# MyBoard_v1.net
KiCad netlist of a schematic drawn in Altium Designer
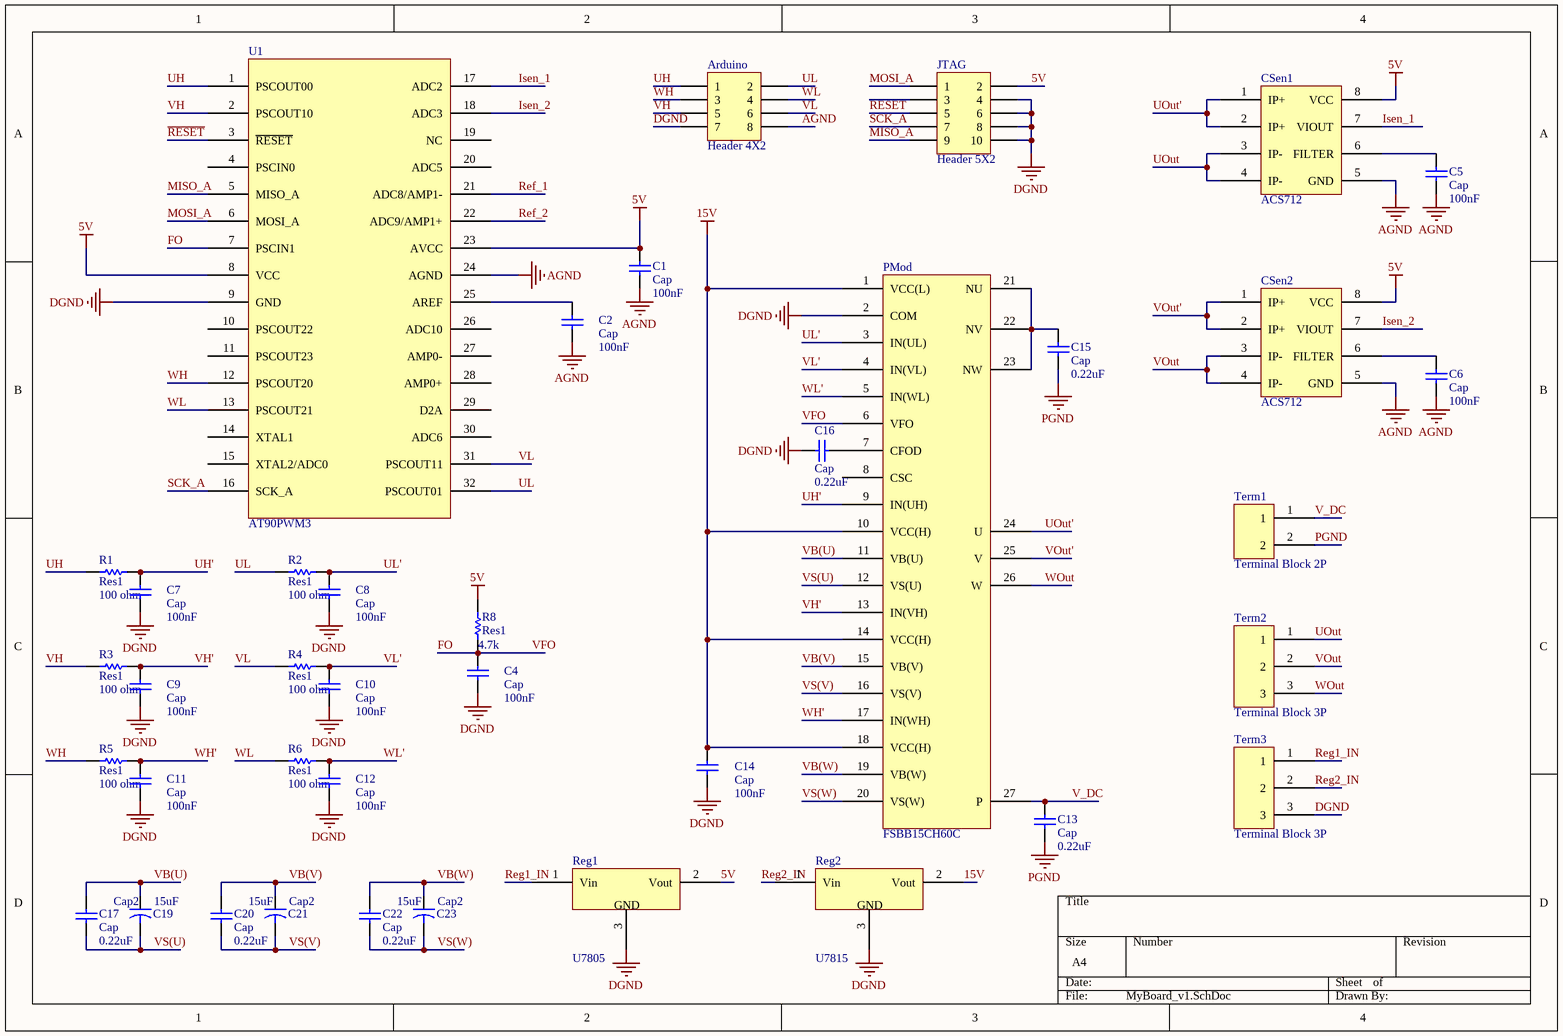
[diagram p0: MyBoard_v1.SchDoc]

(export (version "E")
  (design (tool "Eeschema 10.0.6"))
  (components
    (comp (ref "Arduino")
      (value "Header 4X2")
      (footprint "HDR2X4")
      (description "Header, 4-Pin, Dual row")
      (fields (field (name "PUBLISHER") "Altium Limited"))
      (libsource (lib "Miscellaneous Connectors") (part "Header 4X2"))
    )
    (comp (ref "C1")
      (value "Cap")
      (footprint "NPolar_Cap")
      (description "Capacitor")
      (fields (field (name "ALTIUM_VALUE") "100nF") (field (name "PUBLISHER") "Altium Limited"))
      (libsource (lib "Miscellaneous Devices") (part "Cap"))
    )
    (comp (ref "C2")
      (value "Cap")
      (footprint "NPolar_Cap")
      (description "Capacitor")
      (fields (field (name "ALTIUM_VALUE") "100nF") (field (name "PUBLISHER") "Altium Limited"))
      (libsource (lib "Miscellaneous Devices") (part "Cap"))
    )
    (comp (ref "C4")
      (value "Cap")
      (footprint "NPolar_Cap")
      (description "Capacitor")
      (fields (field (name "ALTIUM_VALUE") "100nF") (field (name "PUBLISHER") "Altium Limited"))
      (libsource (lib "Miscellaneous Devices") (part "Cap"))
    )
    (comp (ref "C5")
      (value "Cap")
      (footprint "NPolar_Cap")
      (description "Capacitor")
      (fields (field (name "ALTIUM_VALUE") "100nF") (field (name "PUBLISHER") "Altium Limited"))
      (libsource (lib "Miscellaneous Devices") (part "Cap"))
    )
    (comp (ref "C6")
      (value "Cap")
      (footprint "NPolar_Cap")
      (description "Capacitor")
      (fields (field (name "ALTIUM_VALUE") "100nF") (field (name "PUBLISHER") "Altium Limited"))
      (libsource (lib "Miscellaneous Devices") (part "Cap"))
    )
    (comp (ref "C7")
      (value "Cap")
      (footprint "NPolar_Cap")
      (description "Capacitor")
      (fields (field (name "ALTIUM_VALUE") "100nF") (field (name "PUBLISHER") "Altium Limited"))
      (libsource (lib "Miscellaneous Devices") (part "Cap"))
    )
    (comp (ref "C8")
      (value "Cap")
      (footprint "NPolar_Cap")
      (description "Capacitor")
      (fields (field (name "ALTIUM_VALUE") "100nF") (field (name "PUBLISHER") "Altium Limited"))
      (libsource (lib "Miscellaneous Devices") (part "Cap"))
    )
    (comp (ref "C9")
      (value "Cap")
      (footprint "NPolar_Cap")
      (description "Capacitor")
      (fields (field (name "ALTIUM_VALUE") "100nF") (field (name "PUBLISHER") "Altium Limited"))
      (libsource (lib "Miscellaneous Devices") (part "Cap"))
    )
    (comp (ref "C10")
      (value "Cap")
      (footprint "NPolar_Cap")
      (description "Capacitor")
      (fields (field (name "ALTIUM_VALUE") "100nF") (field (name "PUBLISHER") "Altium Limited"))
      (libsource (lib "Miscellaneous Devices") (part "Cap"))
    )
    (comp (ref "C11")
      (value "Cap")
      (footprint "NPolar_Cap")
      (description "Capacitor")
      (fields (field (name "ALTIUM_VALUE") "100nF") (field (name "PUBLISHER") "Altium Limited"))
      (libsource (lib "Miscellaneous Devices") (part "Cap"))
    )
    (comp (ref "C12")
      (value "Cap")
      (footprint "NPolar_Cap")
      (description "Capacitor")
      (fields (field (name "ALTIUM_VALUE") "100nF") (field (name "PUBLISHER") "Altium Limited"))
      (libsource (lib "Miscellaneous Devices") (part "Cap"))
    )
    (comp (ref "C13")
      (value "Cap")
      (footprint "NPolar_Cap")
      (description "Capacitor")
      (fields (field (name "ALTIUM_VALUE") "0.22uF") (field (name "PUBLISHER") "Altium Limited"))
      (libsource (lib "Miscellaneous Devices") (part "Cap"))
    )
    (comp (ref "C14")
      (value "Cap")
      (footprint "NPolar_Cap")
      (description "Capacitor")
      (fields (field (name "ALTIUM_VALUE") "100nF") (field (name "PUBLISHER") "Altium Limited"))
      (libsource (lib "Miscellaneous Devices") (part "Cap"))
    )
    (comp (ref "C15")
      (value "Cap")
      (footprint "NPolar_Cap")
      (description "Capacitor")
      (fields (field (name "ALTIUM_VALUE") "0.22uF") (field (name "PUBLISHER") "Altium Limited"))
      (libsource (lib "Miscellaneous Devices") (part "Cap"))
    )
    (comp (ref "C16")
      (value "Cap")
      (footprint "NPolar_Cap")
      (description "Capacitor")
      (fields (field (name "ALTIUM_VALUE") "0.22uF") (field (name "PUBLISHER") "Altium Limited"))
      (libsource (lib "Miscellaneous Devices") (part "Cap"))
    )
    (comp (ref "C17")
      (value "Cap")
      (footprint "NPolar_Cap")
      (description "Capacitor")
      (fields (field (name "ALTIUM_VALUE") "0.22uF") (field (name "PUBLISHER") "Altium Limited"))
      (libsource (lib "Miscellaneous Devices") (part "Cap"))
    )
    (comp (ref "C19")
      (value "Cap2")
      (footprint "Polar_Cap")
      (description "Capacitor")
      (fields (field (name "ALTIUM_VALUE") "15uF") (field (name "PUBLISHER") "Altium Limited"))
      (libsource (lib "Miscellaneous Devices") (part "Cap2"))
    )
    (comp (ref "C20")
      (value "Cap")
      (footprint "NPolar_Cap")
      (description "Capacitor")
      (fields (field (name "ALTIUM_VALUE") "0.22uF") (field (name "PUBLISHER") "Altium Limited"))
      (libsource (lib "Miscellaneous Devices") (part "Cap"))
    )
    (comp (ref "C21")
      (value "Cap2")
      (footprint "Polar_Cap")
      (description "Capacitor")
      (fields (field (name "ALTIUM_VALUE") "15uF") (field (name "PUBLISHER") "Altium Limited"))
      (libsource (lib "Miscellaneous Devices") (part "Cap2"))
    )
    (comp (ref "C22")
      (value "Cap")
      (footprint "NPolar_Cap")
      (description "Capacitor")
      (fields (field (name "ALTIUM_VALUE") "0.22uF") (field (name "PUBLISHER") "Altium Limited"))
      (libsource (lib "Miscellaneous Devices") (part "Cap"))
    )
    (comp (ref "C23")
      (value "Cap2")
      (footprint "Polar_Cap")
      (description "Capacitor")
      (fields (field (name "ALTIUM_VALUE") "15uF") (field (name "PUBLISHER") "Altium Limited"))
      (libsource (lib "Miscellaneous Devices") (part "Cap2"))
    )
    (comp (ref "CSen1")
      (value "ACS712")
      (footprint "FYP:ACS712")
      (libsource (lib "MyBoard_v1") (part "ACS711"))
    )
    (comp (ref "CSen2")
      (value "ACS712")
      (footprint "FYP:ACS712")
      (libsource (lib "MyBoard_v1") (part "ACS711"))
    )
    (comp (ref "JTAG")
      (value "Header 5X2")
      (footprint "HDR2X5")
      (description "Header, 5-Pin, Dual row")
      (fields (field (name "PUBLISHER") "Altium Limited"))
      (libsource (lib "Miscellaneous Connectors") (part "Header 5X2"))
    )
    (comp (ref "PMod")
      (value "FSBB15CH60C")
      (footprint "FYP:FSBB20CH60F")
      (libsource (lib "MyBoard_v1") (part "FSBB15CH60C"))
    )
    (comp (ref "R1")
      (value "Res1")
      (footprint "AXIAL-0.3")
      (description "Resistor")
      (fields (field (name "ALTIUM_VALUE") "100 ohm") (field (name "PUBLISHER") "Altium Limited"))
      (libsource (lib "Miscellaneous Devices") (part "Res1"))
    )
    (comp (ref "R2")
      (value "Res1")
      (footprint "AXIAL-0.3")
      (description "Resistor")
      (fields (field (name "ALTIUM_VALUE") "100 ohm") (field (name "PUBLISHER") "Altium Limited"))
      (libsource (lib "Miscellaneous Devices") (part "Res1"))
    )
    (comp (ref "R3")
      (value "Res1")
      (footprint "AXIAL-0.3")
      (description "Resistor")
      (fields (field (name "ALTIUM_VALUE") "100 ohm") (field (name "PUBLISHER") "Altium Limited"))
      (libsource (lib "Miscellaneous Devices") (part "Res1"))
    )
    (comp (ref "R4")
      (value "Res1")
      (footprint "AXIAL-0.3")
      (description "Resistor")
      (fields (field (name "ALTIUM_VALUE") "100 ohm") (field (name "PUBLISHER") "Altium Limited"))
      (libsource (lib "Miscellaneous Devices") (part "Res1"))
    )
    (comp (ref "R5")
      (value "Res1")
      (footprint "AXIAL-0.3")
      (description "Resistor")
      (fields (field (name "ALTIUM_VALUE") "100 ohm") (field (name "PUBLISHER") "Altium Limited"))
      (libsource (lib "Miscellaneous Devices") (part "Res1"))
    )
    (comp (ref "R6")
      (value "Res1")
      (footprint "AXIAL-0.3")
      (description "Resistor")
      (fields (field (name "ALTIUM_VALUE") "100 ohm") (field (name "PUBLISHER") "Altium Limited"))
      (libsource (lib "Miscellaneous Devices") (part "Res1"))
    )
    (comp (ref "R8")
      (value "Res1")
      (footprint "AXIAL-0.3")
      (description "Resistor")
      (fields (field (name "ALTIUM_VALUE") "4.7k") (field (name "PUBLISHER") "Altium Limited"))
      (libsource (lib "Miscellaneous Devices") (part "Res1"))
    )
    (comp (ref "Reg1") (value "U7805") (footprint "FYP:U7800") (libsource (lib "MyBoard_v1") (part "U7800")))
    (comp (ref "Reg2") (value "U7815") (footprint "FYP:U7800") (libsource (lib "MyBoard_v1") (part "U7800")))
    (comp (ref "Term1")
      (value "Terminal Block 2P")
      (footprint "Terminal Block 2 Pin")
      (libsource (lib "MyBoard_v1") (part "Terminal Block 2P"))
    )
    (comp (ref "Term2")
      (value "Terminal Block 3P")
      (footprint "Terminal Block 3 Pin")
      (libsource (lib "MyBoard_v1") (part "Terminal Block 3P"))
    )
    (comp (ref "Term3")
      (value "Terminal Block 3P")
      (footprint "Terminal Block 3 Pin")
      (libsource (lib "MyBoard_v1") (part "Terminal Block 3P"))
    )
    (comp (ref "U1")
      (value "AT90PWM3")
      (footprint "FYP:AT90PWM3B")
      (libsource (lib "MyBoard_v1") (part "AT90PWM3"))
    )
  )
  (nets
    (net (code "1") (name "/FO") (class "Default")
      (node (ref "C4") (pin "2") (pinfunction "2_2") (pintype "passive"))
      (node (ref "PMod") (pin "6") (pinfunction "VFO_6") (pintype "passive"))
      (node (ref "R8") (pin "1") (pinfunction "1_1") (pintype "passive"))
      (node (ref "U1") (pin "7") (pinfunction "PSCIN1_7") (pintype "passive"))
    )
    (net (code "2") (name "/Isen_1") (class "Default")
      (node (ref "CSen1") (pin "7") (pinfunction "VIOUT_7") (pintype "passive"))
      (node (ref "U1") (pin "17") (pinfunction "ADC2_17") (pintype "passive"))
    )
    (net (code "3") (name "/Isen_2") (class "Default")
      (node (ref "CSen2") (pin "7") (pinfunction "VIOUT_7") (pintype "passive"))
      (node (ref "U1") (pin "18") (pinfunction "ADC3_18") (pintype "passive"))
    )
    (net (code "4") (name "/MISO_A") (class "Default")
      (node (ref "JTAG") (pin "9") (pinfunction "9_9") (pintype "passive"))
      (node (ref "U1") (pin "5") (pinfunction "MISO_A_5") (pintype "passive"))
    )
    (net (code "5") (name "/MOSI_A") (class "Default")
      (node (ref "JTAG") (pin "1") (pinfunction "1_1") (pintype "passive"))
      (node (ref "U1") (pin "6") (pinfunction "MOSI_A_6") (pintype "passive"))
    )
    (net (code "6") (name "/Ref_1") (class "Default")
      (node (ref "U1") (pin "21") (pinfunction "ADC8/AMP1-_21") (pintype "passive"))
    )
    (net (code "7") (name "/Ref_2") (class "Default")
      (node (ref "U1") (pin "22") (pinfunction "ADC9/AMP1+_22") (pintype "passive"))
    )
    (net (code "8") (name "/Reg1_IN") (class "Default")
      (node (ref "Reg1") (pin "1") (pinfunction "Vin_1") (pintype "passive"))
      (node (ref "Term3") (pin "1") (pinfunction "1_1") (pintype "passive"))
    )
    (net (code "9") (name "/Reg2_IN") (class "Default")
      (node (ref "Reg2") (pin "1") (pinfunction "Vin_1") (pintype "passive"))
      (node (ref "Term3") (pin "2") (pinfunction "2_2") (pintype "passive"))
    )
    (net (code "10") (name "/SCK_A") (class "Default")
      (node (ref "JTAG") (pin "7") (pinfunction "7_7") (pintype "passive"))
      (node (ref "U1") (pin "16") (pinfunction "SCK_A_16") (pintype "passive"))
    )
    (net (code "11") (name "/UH") (class "Default")
      (node (ref "Arduino") (pin "1") (pinfunction "1_1") (pintype "passive"))
      (node (ref "R1") (pin "1") (pinfunction "1_1") (pintype "passive"))
      (node (ref "U1") (pin "1") (pinfunction "PSCOUT00_1") (pintype "passive"))
    )
    (net (code "12") (name "/UH'") (class "Default")
      (node (ref "C7") (pin "2") (pinfunction "2_2") (pintype "passive"))
      (node (ref "PMod") (pin "9") (pinfunction "IN(UH)_9") (pintype "passive"))
      (node (ref "R1") (pin "2") (pinfunction "2_2") (pintype "passive"))
    )
    (net (code "13") (name "/UL") (class "Default")
      (node (ref "Arduino") (pin "2") (pinfunction "2_2") (pintype "passive"))
      (node (ref "R2") (pin "1") (pinfunction "1_1") (pintype "passive"))
      (node (ref "U1") (pin "32") (pinfunction "PSCOUT01_32") (pintype "passive"))
    )
    (net (code "14") (name "/UL'") (class "Default")
      (node (ref "C8") (pin "2") (pinfunction "2_2") (pintype "passive"))
      (node (ref "PMod") (pin "3") (pinfunction "IN(UL)_3") (pintype "passive"))
      (node (ref "R2") (pin "2") (pinfunction "2_2") (pintype "passive"))
    )
    (net (code "15") (name "/UOut") (class "Default")
      (node (ref "CSen1") (pin "3") (pinfunction "IP-_3") (pintype "passive"))
      (node (ref "CSen1") (pin "4") (pinfunction "IP-_4") (pintype "passive"))
      (node (ref "Term2") (pin "1") (pinfunction "1_1") (pintype "passive"))
    )
    (net (code "16") (name "/UOut'") (class "Default")
      (node (ref "CSen1") (pin "1") (pinfunction "IP+_1") (pintype "passive"))
      (node (ref "CSen1") (pin "2") (pinfunction "IP+_2") (pintype "passive"))
      (node (ref "PMod") (pin "24") (pinfunction "U_24") (pintype "passive"))
    )
    (net (code "17") (name "/VB(U)") (class "Default")
      (node (ref "C17") (pin "2") (pinfunction "2_2") (pintype "passive"))
      (node (ref "C19") (pin "1") (pinfunction "1_1") (pintype "passive"))
      (node (ref "PMod") (pin "11") (pinfunction "VB(U)_11") (pintype "passive"))
    )
    (net (code "18") (name "/VB(V)") (class "Default")
      (node (ref "C20") (pin "2") (pinfunction "2_2") (pintype "passive"))
      (node (ref "C21") (pin "1") (pinfunction "1_1") (pintype "passive"))
      (node (ref "PMod") (pin "15") (pinfunction "VB(V)_15") (pintype "passive"))
    )
    (net (code "19") (name "/VB(W)") (class "Default")
      (node (ref "C22") (pin "2") (pinfunction "2_2") (pintype "passive"))
      (node (ref "C23") (pin "1") (pinfunction "1_1") (pintype "passive"))
      (node (ref "PMod") (pin "19") (pinfunction "VB(W)_19") (pintype "passive"))
    )
    (net (code "20") (name "/VH") (class "Default")
      (node (ref "Arduino") (pin "5") (pinfunction "5_5") (pintype "passive"))
      (node (ref "R3") (pin "1") (pinfunction "1_1") (pintype "passive"))
      (node (ref "U1") (pin "2") (pinfunction "PSCOUT10_2") (pintype "passive"))
    )
    (net (code "21") (name "/VH'") (class "Default")
      (node (ref "C9") (pin "2") (pinfunction "2_2") (pintype "passive"))
      (node (ref "PMod") (pin "13") (pinfunction "IN(VH)_13") (pintype "passive"))
      (node (ref "R3") (pin "2") (pinfunction "2_2") (pintype "passive"))
    )
    (net (code "22") (name "/VL") (class "Default")
      (node (ref "Arduino") (pin "6") (pinfunction "6_6") (pintype "passive"))
      (node (ref "R4") (pin "1") (pinfunction "1_1") (pintype "passive"))
      (node (ref "U1") (pin "31") (pinfunction "PSCOUT11_31") (pintype "passive"))
    )
    (net (code "23") (name "/VL'") (class "Default")
      (node (ref "C10") (pin "2") (pinfunction "2_2") (pintype "passive"))
      (node (ref "PMod") (pin "4") (pinfunction "IN(VL)_4") (pintype "passive"))
      (node (ref "R4") (pin "2") (pinfunction "2_2") (pintype "passive"))
    )
    (net (code "24") (name "/VOut") (class "Default")
      (node (ref "CSen2") (pin "3") (pinfunction "IP-_3") (pintype "passive"))
      (node (ref "CSen2") (pin "4") (pinfunction "IP-_4") (pintype "passive"))
      (node (ref "Term2") (pin "2") (pinfunction "2_2") (pintype "passive"))
    )
    (net (code "25") (name "/VOut'") (class "Default")
      (node (ref "CSen2") (pin "1") (pinfunction "IP+_1") (pintype "passive"))
      (node (ref "CSen2") (pin "2") (pinfunction "IP+_2") (pintype "passive"))
      (node (ref "PMod") (pin "25") (pinfunction "V_25") (pintype "passive"))
    )
    (net (code "26") (name "/VS(U)") (class "Default")
      (node (ref "C17") (pin "1") (pinfunction "1_1") (pintype "passive"))
      (node (ref "C19") (pin "2") (pinfunction "2_2") (pintype "passive"))
      (node (ref "PMod") (pin "12") (pinfunction "VS(U)_12") (pintype "passive"))
    )
    (net (code "27") (name "/VS(V)") (class "Default")
      (node (ref "C20") (pin "1") (pinfunction "1_1") (pintype "passive"))
      (node (ref "C21") (pin "2") (pinfunction "2_2") (pintype "passive"))
      (node (ref "PMod") (pin "16") (pinfunction "VS(V)_16") (pintype "passive"))
    )
    (net (code "28") (name "/VS(W)") (class "Default")
      (node (ref "C22") (pin "1") (pinfunction "1_1") (pintype "passive"))
      (node (ref "C23") (pin "2") (pinfunction "2_2") (pintype "passive"))
      (node (ref "PMod") (pin "20") (pinfunction "VS(W)_20") (pintype "passive"))
    )
    (net (code "29") (name "/V_DC") (class "Default")
      (node (ref "C13") (pin "2") (pinfunction "2_2") (pintype "passive"))
      (node (ref "PMod") (pin "27") (pinfunction "P_27") (pintype "passive"))
      (node (ref "Term1") (pin "1") (pinfunction "1_1") (pintype "passive"))
    )
    (net (code "30") (name "/WH") (class "Default")
      (node (ref "Arduino") (pin "3") (pinfunction "3_3") (pintype "passive"))
      (node (ref "R5") (pin "1") (pinfunction "1_1") (pintype "passive"))
      (node (ref "U1") (pin "12") (pinfunction "PSCOUT20_12") (pintype "passive"))
    )
    (net (code "31") (name "/WH'") (class "Default")
      (node (ref "C11") (pin "2") (pinfunction "2_2") (pintype "passive"))
      (node (ref "PMod") (pin "17") (pinfunction "IN(WH)_17") (pintype "passive"))
      (node (ref "R5") (pin "2") (pinfunction "2_2") (pintype "passive"))
    )
    (net (code "32") (name "/WL") (class "Default")
      (node (ref "Arduino") (pin "4") (pinfunction "4_4") (pintype "passive"))
      (node (ref "R6") (pin "1") (pinfunction "1_1") (pintype "passive"))
      (node (ref "U1") (pin "13") (pinfunction "PSCOUT21_13") (pintype "passive"))
    )
    (net (code "33") (name "/WL'") (class "Default")
      (node (ref "C12") (pin "2") (pinfunction "2_2") (pintype "passive"))
      (node (ref "PMod") (pin "5") (pinfunction "IN(WL)_5") (pintype "passive"))
      (node (ref "R6") (pin "2") (pinfunction "2_2") (pintype "passive"))
    )
    (net (code "34") (name "/WOut") (class "Default")
      (node (ref "PMod") (pin "26") (pinfunction "W_26") (pintype "passive"))
      (node (ref "Term2") (pin "3") (pinfunction "3_3") (pintype "passive"))
    )
    (net (code "35") (name "/~{RESET}") (class "Default")
      (node (ref "JTAG") (pin "5") (pinfunction "5_5") (pintype "passive"))
      (node (ref "U1") (pin "3") (pinfunction "~{RESET}_3") (pintype "passive"))
    )
    (net (code "36") (name "5V") (class "Default")
      (node (ref "C1") (pin "2") (pinfunction "2_2") (pintype "passive"))
      (node (ref "CSen1") (pin "8") (pinfunction "VCC_8") (pintype "passive"))
      (node (ref "CSen2") (pin "8") (pinfunction "VCC_8") (pintype "passive"))
      (node (ref "JTAG") (pin "2") (pinfunction "2_2") (pintype "passive"))
      (node (ref "R8") (pin "2") (pinfunction "2_2") (pintype "passive"))
      (node (ref "Reg1") (pin "2") (pinfunction "Vout_2") (pintype "passive"))
      (node (ref "U1") (pin "23") (pinfunction "AVCC_23") (pintype "passive"))
      (node (ref "U1") (pin "8") (pinfunction "VCC_8") (pintype "passive"))
    )
    (net (code "37") (name "15V") (class "Default")
      (node (ref "C14") (pin "2") (pinfunction "2_2") (pintype "passive"))
      (node (ref "PMod") (pin "1") (pinfunction "VCC(L)_1") (pintype "passive"))
      (node (ref "PMod") (pin "10") (pinfunction "VCC(H)_10") (pintype "passive"))
      (node (ref "PMod") (pin "14") (pinfunction "VCC(H)_14") (pintype "passive"))
      (node (ref "PMod") (pin "18") (pinfunction "VCC(H)_18") (pintype "passive"))
      (node (ref "Reg2") (pin "2") (pinfunction "Vout_2") (pintype "passive"))
    )
    (net (code "38") (name "AGND") (class "Default")
      (node (ref "Arduino") (pin "8") (pinfunction "8_8") (pintype "passive"))
      (node (ref "C1") (pin "1") (pinfunction "1_1") (pintype "passive"))
      (node (ref "C2") (pin "1") (pinfunction "1_1") (pintype "passive"))
      (node (ref "C5") (pin "1") (pinfunction "1_1") (pintype "passive"))
      (node (ref "C6") (pin "1") (pinfunction "1_1") (pintype "passive"))
      (node (ref "CSen1") (pin "5") (pinfunction "GND_5") (pintype "passive"))
      (node (ref "CSen2") (pin "5") (pinfunction "GND_5") (pintype "passive"))
      (node (ref "U1") (pin "24") (pinfunction "AGND_24") (pintype "passive"))
    )
    (net (code "39") (name "DGND") (class "Default")
      (node (ref "Arduino") (pin "7") (pinfunction "7_7") (pintype "passive"))
      (node (ref "C10") (pin "1") (pinfunction "1_1") (pintype "passive"))
      (node (ref "C11") (pin "1") (pinfunction "1_1") (pintype "passive"))
      (node (ref "C12") (pin "1") (pinfunction "1_1") (pintype "passive"))
      (node (ref "C14") (pin "1") (pinfunction "1_1") (pintype "passive"))
      (node (ref "C16") (pin "1") (pinfunction "1_1") (pintype "passive"))
      (node (ref "C4") (pin "1") (pinfunction "1_1") (pintype "passive"))
      (node (ref "C7") (pin "1") (pinfunction "1_1") (pintype "passive"))
      (node (ref "C8") (pin "1") (pinfunction "1_1") (pintype "passive"))
      (node (ref "C9") (pin "1") (pinfunction "1_1") (pintype "passive"))
      (node (ref "JTAG") (pin "10") (pinfunction "10_10") (pintype "passive"))
      (node (ref "JTAG") (pin "4") (pinfunction "4_4") (pintype "passive"))
      (node (ref "JTAG") (pin "6") (pinfunction "6_6") (pintype "passive"))
      (node (ref "JTAG") (pin "8") (pinfunction "8_8") (pintype "passive"))
      (node (ref "PMod") (pin "2") (pinfunction "COM_2") (pintype "passive"))
      (node (ref "Reg1") (pin "3") (pinfunction "GND_3") (pintype "power_in"))
      (node (ref "Reg2") (pin "3") (pinfunction "GND_3") (pintype "power_in"))
      (node (ref "Term3") (pin "3") (pinfunction "3_3") (pintype "passive"))
      (node (ref "U1") (pin "9") (pinfunction "GND_9") (pintype "passive"))
    )
    (net (code "40") (name "Net-(CSen1-FILTER)") (class "Default")
      (node (ref "C5") (pin "2") (pinfunction "2_2") (pintype "passive"))
      (node (ref "CSen1") (pin "6") (pinfunction "FILTER_6") (pintype "passive"))
    )
    (net (code "41") (name "Net-(CSen2-FILTER)") (class "Default")
      (node (ref "C6") (pin "2") (pinfunction "2_2") (pintype "passive"))
      (node (ref "CSen2") (pin "6") (pinfunction "FILTER_6") (pintype "passive"))
    )
    (net (code "42") (name "Net-(PMod-CFOD)") (class "Default")
      (node (ref "C16") (pin "2") (pinfunction "2_2") (pintype "passive"))
      (node (ref "PMod") (pin "7") (pinfunction "CFOD_7") (pintype "passive"))
    )
    (net (code "43") (name "Net-(PMod-NU)") (class "Default")
      (node (ref "C15") (pin "2") (pinfunction "2_2") (pintype "passive"))
      (node (ref "PMod") (pin "21") (pinfunction "NU_21") (pintype "passive"))
      (node (ref "PMod") (pin "22") (pinfunction "NV_22") (pintype "passive"))
      (node (ref "PMod") (pin "23") (pinfunction "NW_23") (pintype "passive"))
    )
    (net (code "44") (name "Net-(U1-AREF)") (class "Default")
      (node (ref "C2") (pin "2") (pinfunction "2_2") (pintype "passive"))
      (node (ref "U1") (pin "25") (pinfunction "AREF_25") (pintype "passive"))
    )
    (net (code "45") (name "PGND") (class "Default")
      (node (ref "C13") (pin "1") (pinfunction "1_1") (pintype "passive"))
      (node (ref "C15") (pin "1") (pinfunction "1_1") (pintype "passive"))
      (node (ref "Term1") (pin "2") (pinfunction "2_2") (pintype "passive"))
    )
    (net (code "46") (name "unconnected-(JTAG-Pad3)") (class "Default")
      (node (ref "JTAG") (pin "3") (pinfunction "3_3") (pintype "passive"))
    )
    (net (code "47") (name "unconnected-(PMod-CSC-Pad8)") (class "Default")
      (node (ref "PMod") (pin "8") (pinfunction "CSC_8") (pintype "passive"))
    )
    (net (code "48") (name "unconnected-(U1-ADC5-Pad20)") (class "Default")
      (node (ref "U1") (pin "20") (pinfunction "ADC5_20") (pintype "passive"))
    )
    (net (code "49") (name "unconnected-(U1-ADC6-Pad30)") (class "Default")
      (node (ref "U1") (pin "30") (pinfunction "ADC6_30") (pintype "passive"))
    )
    (net (code "50") (name "unconnected-(U1-ADC10-Pad26)") (class "Default")
      (node (ref "U1") (pin "26") (pinfunction "ADC10_26") (pintype "passive"))
    )
    (net (code "51") (name "unconnected-(U1-AMP0+-Pad28)") (class "Default")
      (node (ref "U1") (pin "28") (pinfunction "AMP0+_28") (pintype "passive"))
    )
    (net (code "52") (name "unconnected-(U1-AMP0--Pad27)") (class "Default")
      (node (ref "U1") (pin "27") (pinfunction "AMP0-_27") (pintype "passive"))
    )
    (net (code "53") (name "unconnected-(U1-D2A-Pad29)") (class "Default")
      (node (ref "U1") (pin "29") (pinfunction "D2A_29") (pintype "passive"))
    )
    (net (code "54") (name "unconnected-(U1-NC-Pad19)") (class "Default")
      (node (ref "U1") (pin "19") (pinfunction "NC_19") (pintype "passive"))
    )
    (net (code "55") (name "unconnected-(U1-PSCIN0-Pad4)") (class "Default")
      (node (ref "U1") (pin "4") (pinfunction "PSCIN0_4") (pintype "passive"))
    )
    (net (code "56") (name "unconnected-(U1-PSCOUT22-Pad10)") (class "Default")
      (node (ref "U1") (pin "10") (pinfunction "PSCOUT22_10") (pintype "passive"))
    )
    (net (code "57") (name "unconnected-(U1-PSCOUT23-Pad11)") (class "Default")
      (node (ref "U1") (pin "11") (pinfunction "PSCOUT23_11") (pintype "passive"))
    )
    (net (code "58") (name "unconnected-(U1-XTAL1-Pad14)") (class "Default")
      (node (ref "U1") (pin "14") (pinfunction "XTAL1_14") (pintype "passive"))
    )
    (net (code "59") (name "unconnected-(U1-XTAL2{slash}ADC0-Pad15)") (class "Default")
      (node (ref "U1") (pin "15") (pinfunction "XTAL2/ADC0_15") (pintype "passive"))
    )
  )
)
